# ISP-Adapter.net
KiCad netlist of a schematic drawn in EAGLE
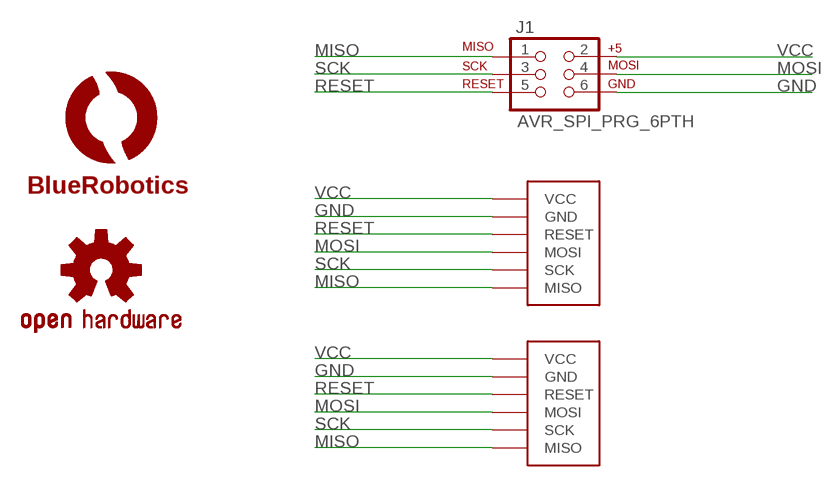
[diagram p0: schematic, sheet 1]

(export (version "E")
  (design (tool "Eeschema 10.0.6"))
  (components
    (comp (ref "J1")
      (value "AVR_SPI_PRG_6PTH")
      (footprint "eagle-import:2X3")
      (libsource (lib "eagle-import") (part "AVR_SPI_PRG_6PTH"))
    )
    (comp (ref "LOGO1")
      (value "OSHW-LOGOS")
      (footprint "eagle-import:OSHW-LOGO-S")
      (libsource (lib "eagle-import") (part "OSHW-LOGOS"))
    )
    (comp (ref "U$1")
      (value "AVR-ISPTINY-SMD")
      (footprint "eagle-import:AVR-ISP-TINY")
      (libsource (lib "eagle-import") (part "AVR-ISPTINY-SMD"))
    )
    (comp (ref "U$2")
      (value "AVR-ISPTINY-SMD-POGO")
      (footprint "eagle-import:AVR-ISP-TINY-POGO")
      (libsource (lib "eagle-import") (part "AVR-ISPTINY-SMD-POGO"))
    )
    (comp (ref "U$3")
      (value "LOGOBR-LOGO-S")
      (footprint "eagle-import:BR-LOGO-SMALL")
      (libsource (lib "eagle-import") (part "LOGOBR-LOGO-S"))
    )
  )
  (nets
    (net (code "1") (name "/GND") (class "Default")
      (node (ref "J1") (pin "6") (pinfunction "6_6") (pintype "passive"))
      (node (ref "U$1") (pin "GND") (pinfunction "GND_GND") (pintype "power_in"))
      (node (ref "U$2") (pin "GND") (pinfunction "GND_GND") (pintype "power_in"))
    )
    (net (code "2") (name "/MISO") (class "Default")
      (node (ref "J1") (pin "1") (pinfunction "1_1") (pintype "passive"))
      (node (ref "U$1") (pin "MISO") (pinfunction "MISO_MISO") (pintype "bidirectional"))
      (node (ref "U$2") (pin "MISO") (pinfunction "MISO_MISO") (pintype "bidirectional"))
    )
    (net (code "3") (name "/MOSI") (class "Default")
      (node (ref "J1") (pin "4") (pinfunction "4_4") (pintype "passive"))
      (node (ref "U$1") (pin "MOSI") (pinfunction "MOSI_MOSI") (pintype "bidirectional"))
      (node (ref "U$2") (pin "MOSI") (pinfunction "MOSI_MOSI") (pintype "bidirectional"))
    )
    (net (code "4") (name "/RESET") (class "Default")
      (node (ref "J1") (pin "5") (pinfunction "5_5") (pintype "passive"))
      (node (ref "U$1") (pin "RESET") (pinfunction "RESET_RESET") (pintype "bidirectional"))
      (node (ref "U$2") (pin "RESET") (pinfunction "RESET_RESET") (pintype "bidirectional"))
    )
    (net (code "5") (name "/SCK") (class "Default")
      (node (ref "J1") (pin "3") (pinfunction "3_3") (pintype "passive"))
      (node (ref "U$1") (pin "SCK") (pinfunction "SCK_SCK") (pintype "bidirectional"))
      (node (ref "U$2") (pin "SCK") (pinfunction "SCK_SCK") (pintype "bidirectional"))
    )
    (net (code "6") (name "/VCC") (class "Default")
      (node (ref "J1") (pin "2") (pinfunction "2_2") (pintype "passive"))
      (node (ref "U$1") (pin "VCC") (pinfunction "VCC_VCC") (pintype "power_in"))
      (node (ref "U$2") (pin "VCC") (pinfunction "VCC_VCC") (pintype "power_in"))
    )
  )
)
